# ODB2.net
KiCad netlist of a schematic drawn in EAGLE
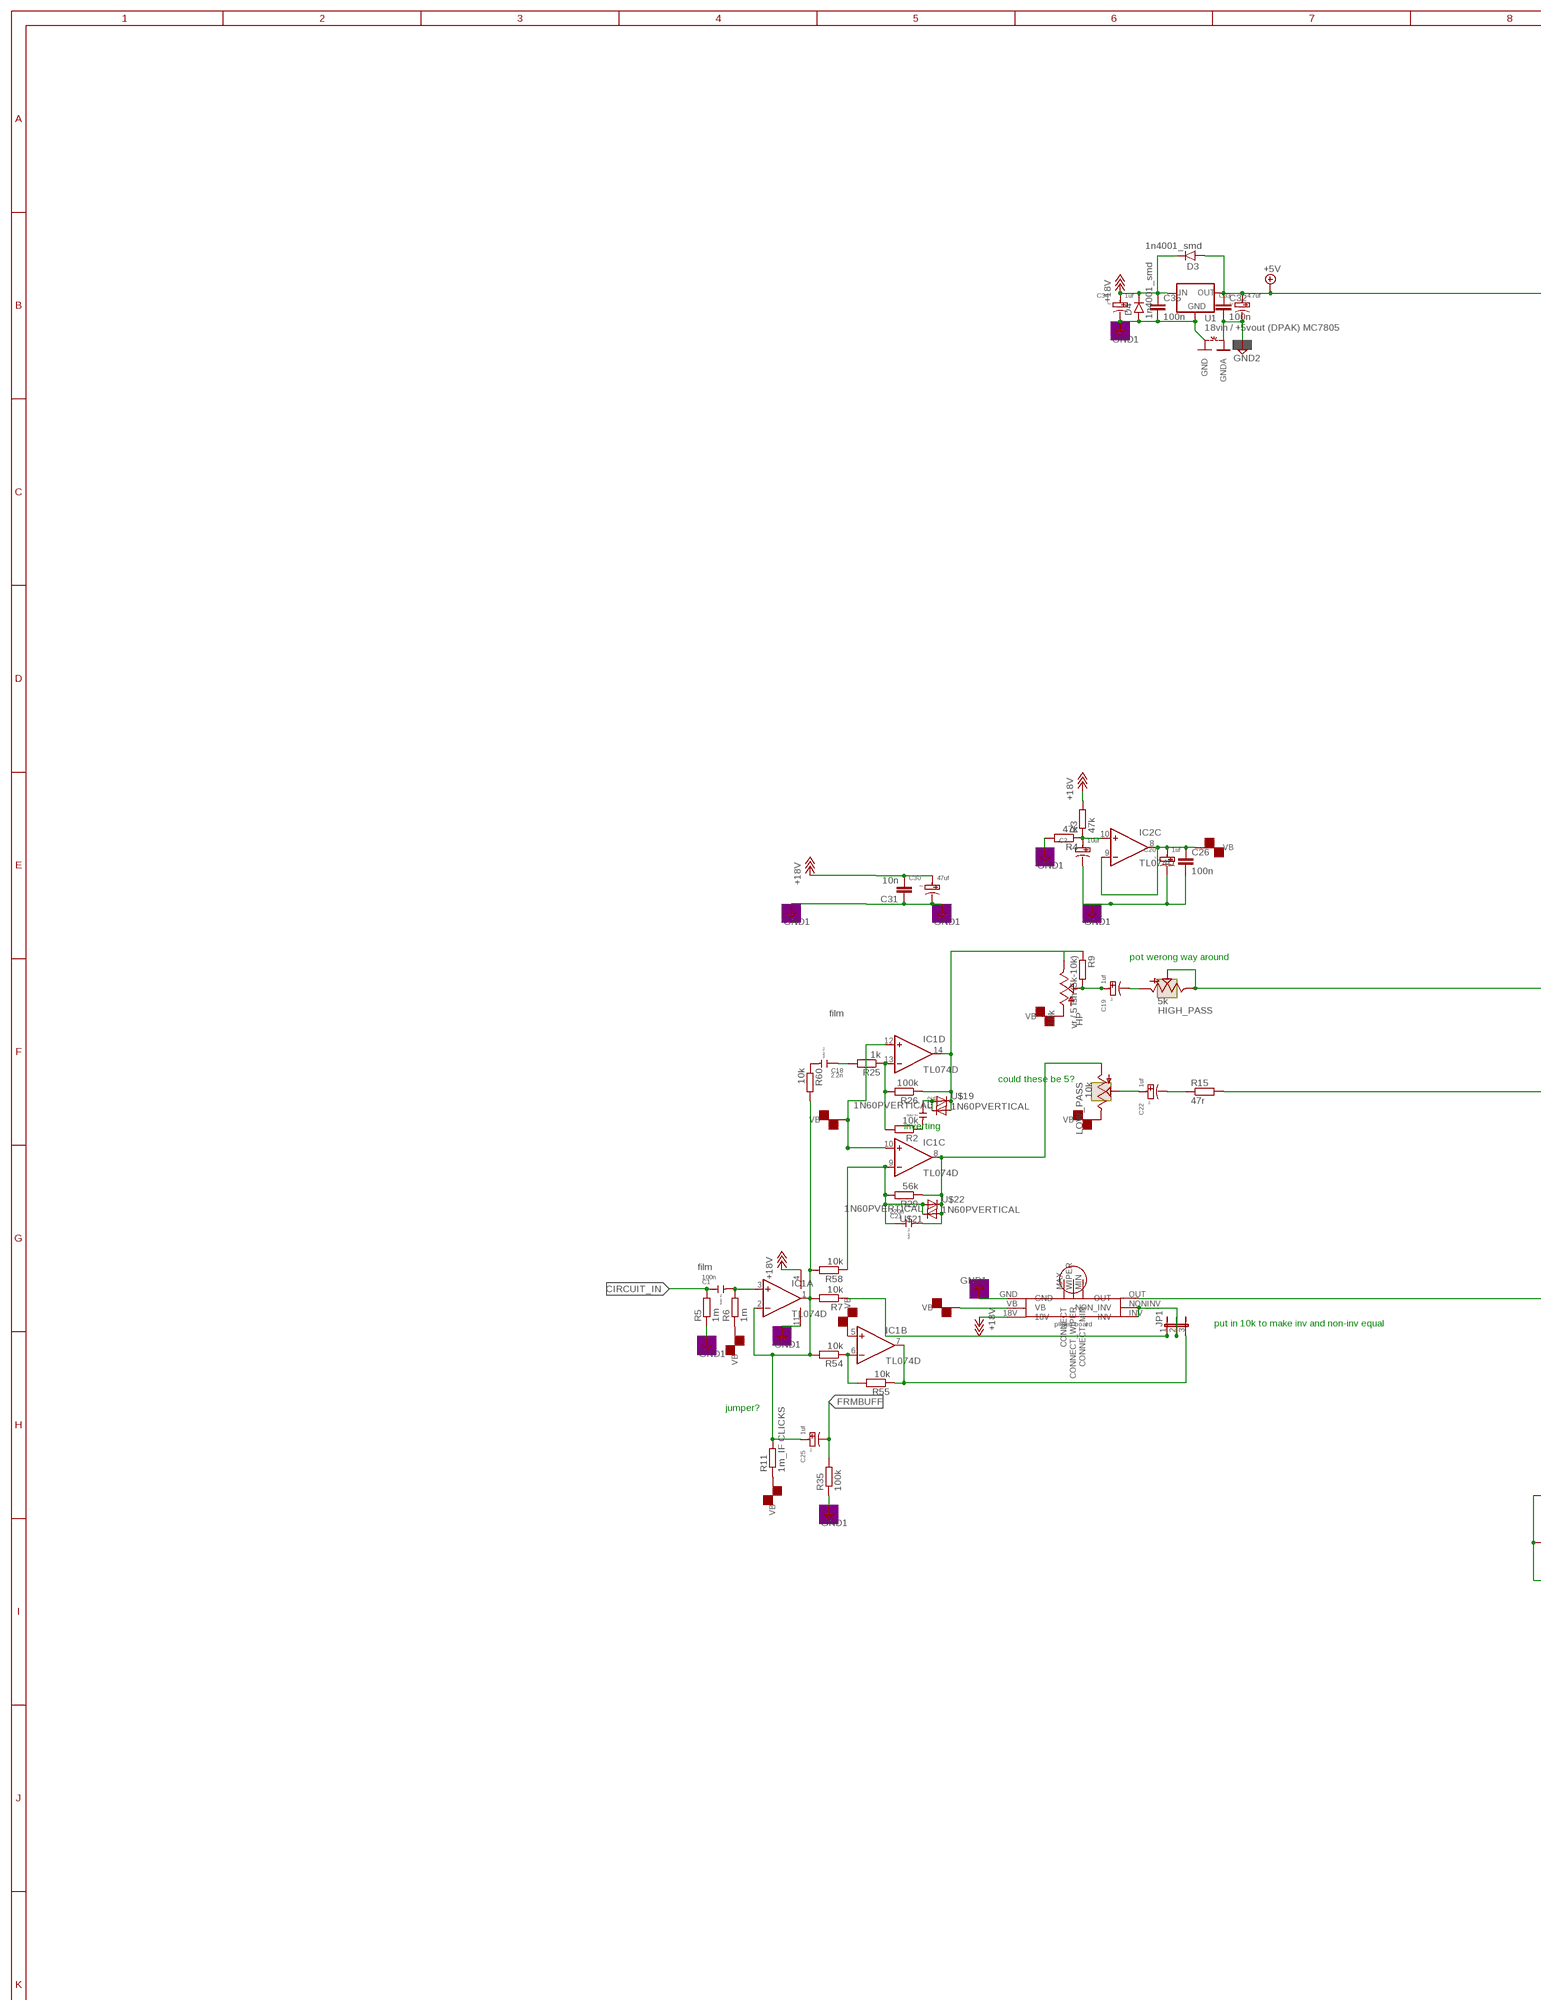
[diagram p0: schematic, sheet 1, part 1 of 3]
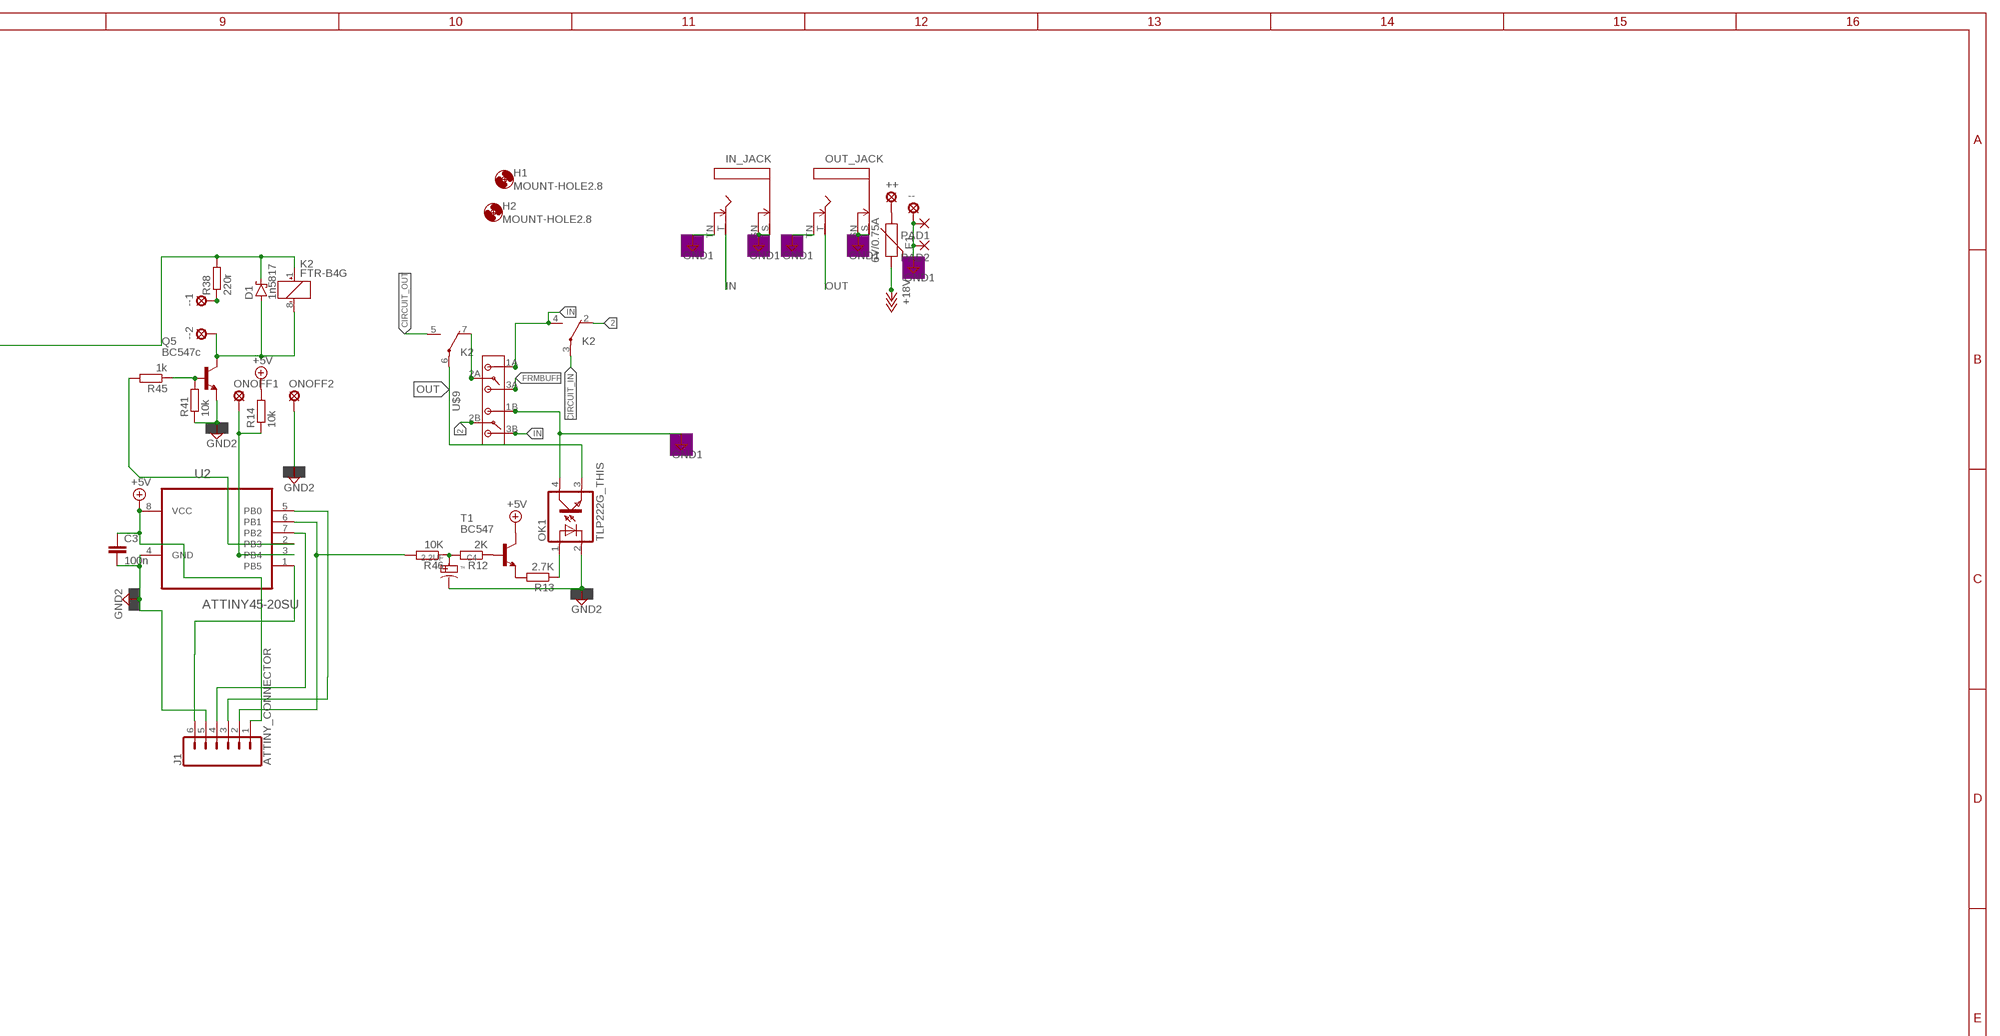
[diagram p1: schematic, sheet 1, part 2 of 3]
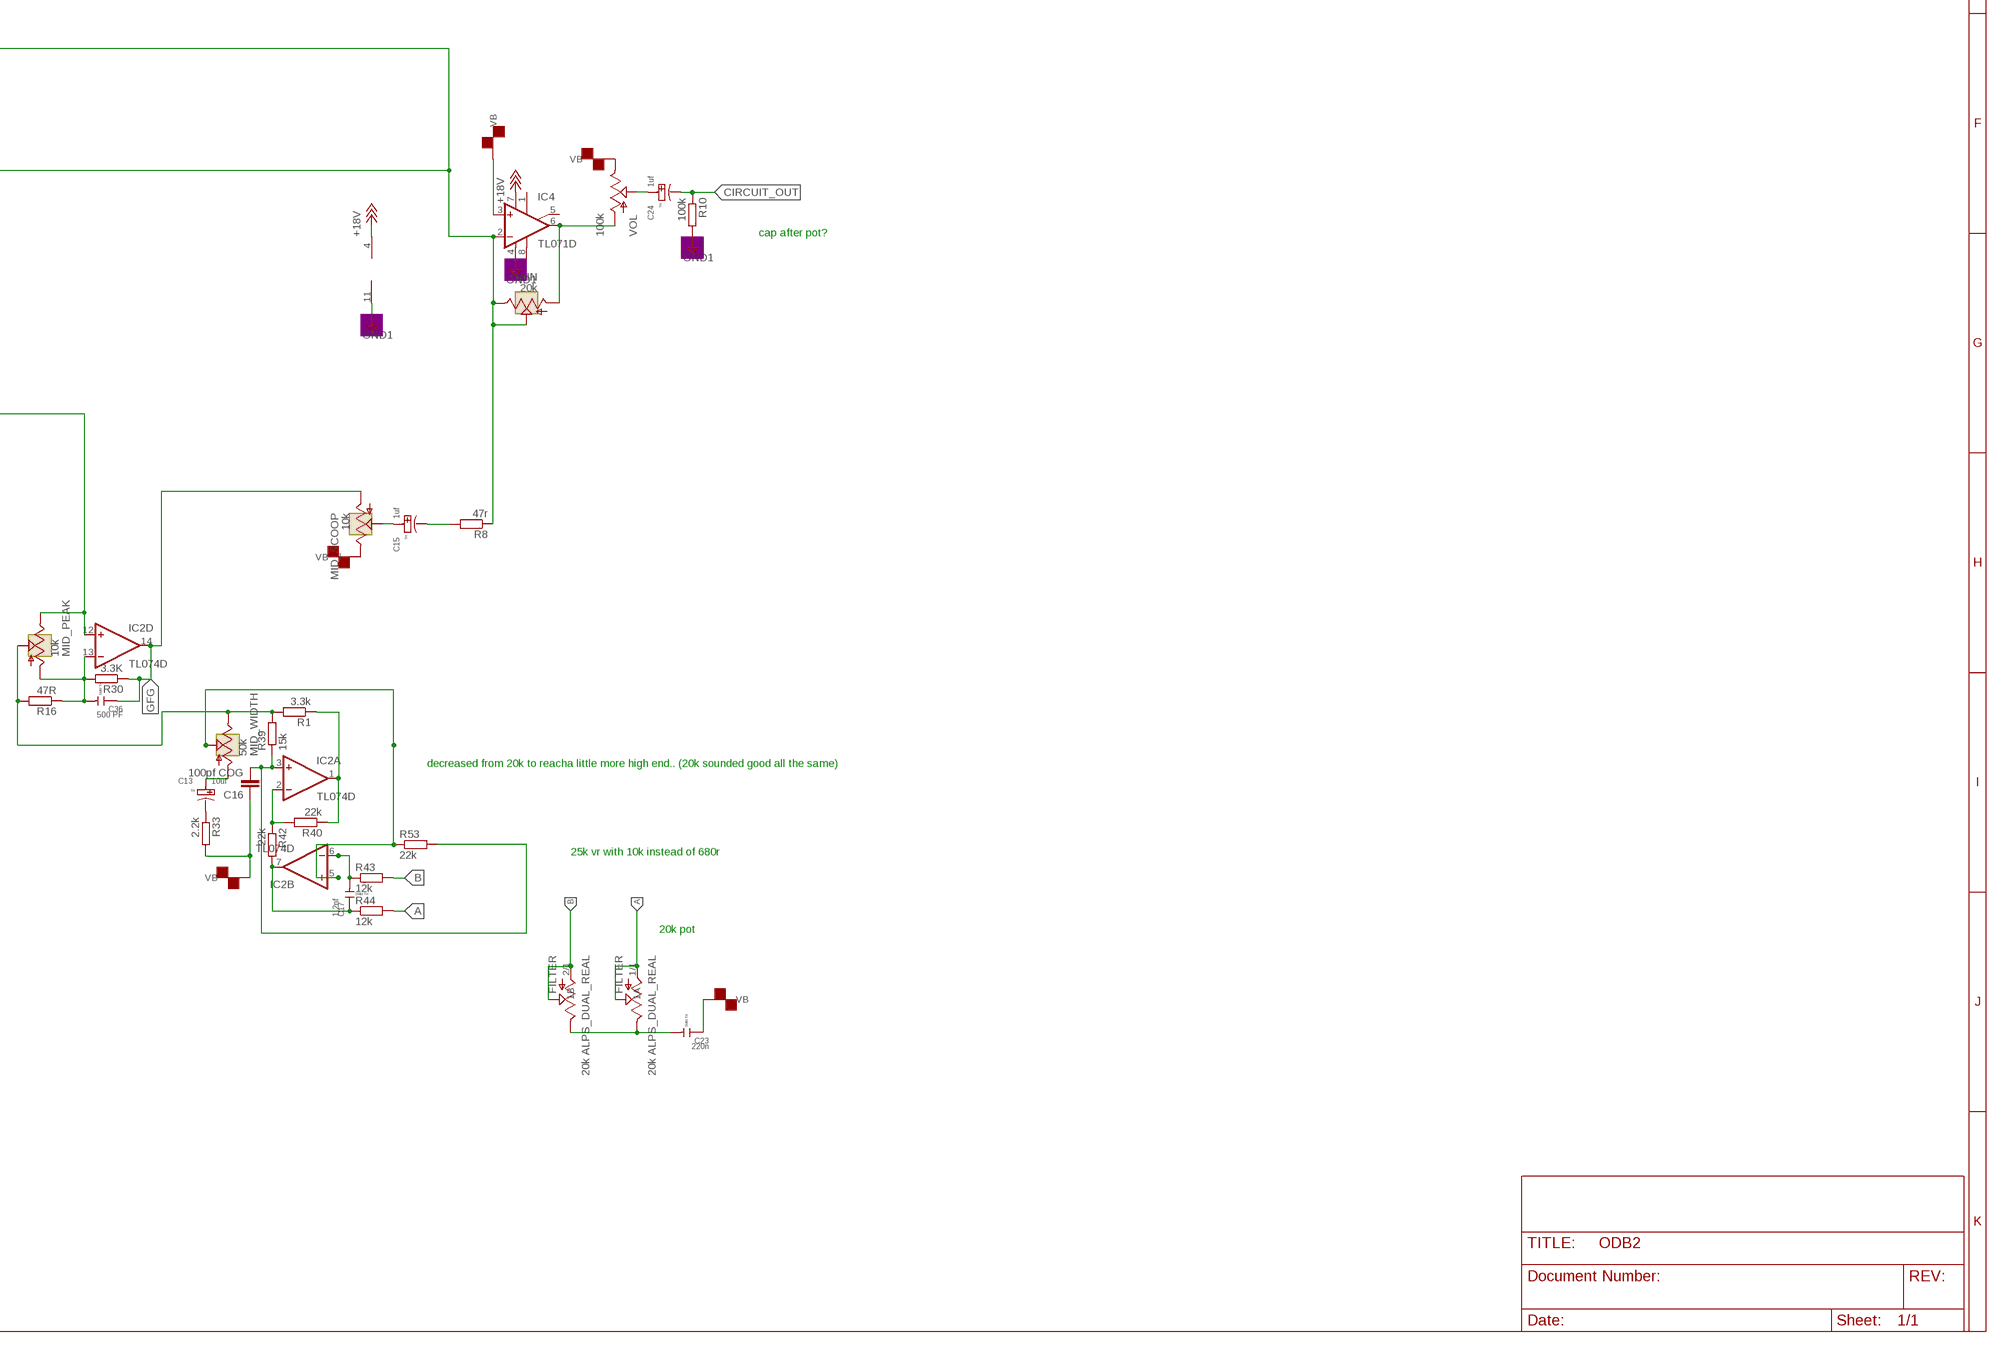
[diagram p2: schematic, sheet 1, part 3 of 3]

(export (version "E")
  (design (tool "Eeschema 10.0.6"))
  (components
    (comp (ref "++")
      (value "LSP10")
      (footprint "eagle-import:LSP10")
      (libsource (lib "eagle-import") (part "LSP10"))
    )
    (comp (ref "--")
      (value "LSP10")
      (footprint "eagle-import:LSP10")
      (libsource (lib "eagle-import") (part "LSP10"))
    )
    (comp (ref "--1")
      (value "LSP10")
      (footprint "eagle-import:LSP10")
      (libsource (lib "eagle-import") (part "LSP10"))
    )
    (comp (ref "--2")
      (value "LSP10")
      (footprint "eagle-import:LSP10")
      (libsource (lib "eagle-import") (part "LSP10"))
    )
    (comp (ref "C1")
      (value "100n")
      (footprint "eagle-import:CERAMIC-5MM")
      (fields (field (name "PACKAGE") "5MM TH"))
      (libsource (lib "eagle-import") (part "THRU_HOLE_5MM_SPACING"))
    )
    (comp (ref "C2")
      (value "10uf")
      (footprint "eagle-import:PC-D5.3MM")
      (fields (field (name "PACKAGE") "TH"))
      (libsource (lib "eagle-import") (part "THRU-HOLE-POLARIZED"))
    )
    (comp (ref "C3")
      (value "100n")
      (footprint "eagle-import:C1206")
      (libsource (lib "eagle-import") (part "resistor_348_C-EUC1206"))
    )
    (comp (ref "C4")
      (value "2.2UF")
      (footprint "eagle-import:PC-D5.3MM")
      (fields (field (name "PACKAGE") "TH"))
      (libsource (lib "eagle-import") (part "THRU-HOLE-POLARIZED"))
    )
    (comp (ref "C12")
      (value "1n")
      (footprint "eagle-import:CERAMIC-5MM")
      (fields (field (name "PACKAGE") "5MM TH"))
      (libsource (lib "eagle-import") (part "THRU_HOLE_5MM_SPACING"))
    )
    (comp (ref "C13")
      (value "10uf")
      (footprint "eagle-import:PC-D5.3MM")
      (fields (field (name "PACKAGE") "TH"))
      (libsource (lib "eagle-import") (part "THRU-HOLE-POLARIZED"))
    )
    (comp (ref "C15")
      (value "1uf")
      (footprint "eagle-import:PC-D5.3MM")
      (fields (field (name "PACKAGE") "TH"))
      (libsource (lib "eagle-import") (part "THRU-HOLE-POLARIZED"))
    )
    (comp (ref "C16")
      (value "100pf COG")
      (footprint "eagle-import:C1206")
      (libsource (lib "eagle-import") (part "resistor_348_C-EUC1206"))
    )
    (comp (ref "C17")
      (value "1.2nf")
      (footprint "eagle-import:CERAMIC-5MM")
      (fields (field (name "PACKAGE") "5MM TH"))
      (libsource (lib "eagle-import") (part "THRU_HOLE_5MM_SPACING"))
    )
    (comp (ref "C18")
      (value "2.2n")
      (footprint "eagle-import:CERAMIC-5MM")
      (fields (field (name "PACKAGE") "5MM TH"))
      (libsource (lib "eagle-import") (part "THRU_HOLE_5MM_SPACING"))
    )
    (comp (ref "C19")
      (value "1uf")
      (footprint "eagle-import:PC-D5.3MM")
      (fields (field (name "PACKAGE") "TH"))
      (libsource (lib "eagle-import") (part "THRU-HOLE-POLARIZED"))
    )
    (comp (ref "C20")
      (value "1uf")
      (footprint "eagle-import:PC-D5.3MM")
      (fields (field (name "PACKAGE") "TH"))
      (libsource (lib "eagle-import") (part "THRU-HOLE-POLARIZED"))
    )
    (comp (ref "C21")
      (value "220n")
      (footprint "eagle-import:CERAMIC-5MM")
      (fields (field (name "PACKAGE") "5MM TH"))
      (libsource (lib "eagle-import") (part "THRU_HOLE_5MM_SPACING"))
    )
    (comp (ref "C22")
      (value "1uf")
      (footprint "eagle-import:PC-D5.3MM")
      (fields (field (name "PACKAGE") "TH"))
      (libsource (lib "eagle-import") (part "THRU-HOLE-POLARIZED"))
    )
    (comp (ref "C23")
      (value "220n")
      (footprint "eagle-import:CERAMIC-5MM")
      (fields (field (name "PACKAGE") "5MM TH"))
      (libsource (lib "eagle-import") (part "THRU_HOLE_5MM_SPACING"))
    )
    (comp (ref "C24")
      (value "1uf")
      (footprint "eagle-import:PC-D5.3MM")
      (fields (field (name "PACKAGE") "TH"))
      (libsource (lib "eagle-import") (part "THRU-HOLE-POLARIZED"))
    )
    (comp (ref "C25")
      (value "1uf")
      (footprint "eagle-import:PC-D5.3MM")
      (fields (field (name "PACKAGE") "TH"))
      (libsource (lib "eagle-import") (part "THRU-HOLE-POLARIZED"))
    )
    (comp (ref "C26")
      (value "100n")
      (footprint "eagle-import:C1206")
      (libsource (lib "eagle-import") (part "resistor_348_C-EUC1206"))
    )
    (comp (ref "C30")
      (value "47uf")
      (footprint "eagle-import:PC-D5.3MM")
      (fields (field (name "PACKAGE") "TH"))
      (libsource (lib "eagle-import") (part "THRU-HOLE-POLARIZED"))
    )
    (comp (ref "C31")
      (value "10n")
      (footprint "eagle-import:C1206")
      (libsource (lib "eagle-import") (part "C-EUC1206"))
    )
    (comp (ref "C32")
      (value "100n")
      (footprint "eagle-import:C1206")
      (libsource (lib "eagle-import") (part "resistor_348_C-EUC1206"))
    )
    (comp (ref "C33")
      (value "4.7uf")
      (footprint "eagle-import:PC-D5.3MM")
      (fields (field (name "PACKAGE") "TH"))
      (libsource (lib "eagle-import") (part "THRU-HOLE-POLARIZED"))
    )
    (comp (ref "C34")
      (value "1uf")
      (footprint "eagle-import:PC-D5.3MM")
      (fields (field (name "PACKAGE") "TH"))
      (libsource (lib "eagle-import") (part "THRU-HOLE-POLARIZED"))
    )
    (comp (ref "C35")
      (value "100n")
      (footprint "eagle-import:C1206")
      (libsource (lib "eagle-import") (part "resistor_348_C-EUC1206"))
    )
    (comp (ref "C36")
      (value "500 PF")
      (footprint "eagle-import:CERAMIC-5MM")
      (fields (field (name "PACKAGE") "5MM TH"))
      (libsource (lib "eagle-import") (part "THRU_HOLE_5MM_SPACING"))
    )
    (comp (ref "D1")
      (value "1n5817")
      (footprint "eagle-import:SMB")
      (libsource (lib "eagle-import") (part "SCHOTTKY-DIODESMD"))
    )
    (comp (ref "D3")
      (value "1n4001_smd")
      (footprint "eagle-import:DO41-1")
      (libsource (lib "eagle-import") (part "1N400X.1"))
    )
    (comp (ref "D4")
      (value "1n4001_smd")
      (footprint "eagle-import:DO41-1")
      (libsource (lib "eagle-import") (part "1N400X.1"))
    )
    (comp (ref "F1")
      (value "6V/0.75A")
      (footprint "eagle-import:1206")
      (libsource (lib "eagle-import") (part "PPTC_THREE-QUARTER-AMP"))
    )
    (comp (ref "FILTER")
      (value "20k ALPS_DUAL_REAL")
      (footprint "eagle-import:ALPS_QUAD")
      (libsource (lib "eagle-import") (part "ALPS_DUAL_REAL"))
    )
    (comp (ref "GAIN")
      (value "20k")
      (footprint "eagle-import:3223G")
      (libsource (lib "eagle-import") (part "TRIM_US-3223G"))
    )
    (comp (ref "H1")
      (value "MOUNT-HOLE2.8")
      (footprint "eagle-import:2,8")
      (libsource (lib "eagle-import") (part "MOUNT-HOLE2.8"))
    )
    (comp (ref "H2")
      (value "MOUNT-HOLE2.8")
      (footprint "eagle-import:2,8")
      (libsource (lib "eagle-import") (part "MOUNT-HOLE2.8"))
    )
    (comp (ref "HIGH_PASS")
      (value "5k")
      (footprint "eagle-import:3223G")
      (libsource (lib "eagle-import") (part "TRIM_US-3223G"))
    )
    (comp (ref "HP")
      (value "10k")
      (footprint "eagle-import:ALPS_POT")
      (libsource (lib "eagle-import") (part "POT"))
    )
    (comp (ref "IC1")
      (value "TL074D")
      (footprint "eagle-import:SO14")
      (libsource (lib "eagle-import") (part "TL074D"))
    )
    (comp (ref "IC2")
      (value "TL074D")
      (footprint "eagle-import:SO14")
      (libsource (lib "eagle-import") (part "TL074D"))
    )
    (comp (ref "IC4")
      (value "TL071D")
      (footprint "eagle-import:SO08")
      (libsource (lib "eagle-import") (part "TL071D"))
    )
    (comp (ref "IN_JACK")
      (value "MMMONNNNOHOLES")
      (footprint "eagle-import:MONONOHOLES")
      (libsource (lib "eagle-import") (part "MMMONNNNOHOLES"))
    )
    (comp (ref "J1")
      (value "ATTINY_CONNECTOR")
      (footprint "eagle-import:1X06_LONGPADS")
      (libsource (lib "eagle-import") (part "CONN_06LONGPADS"))
    )
    (comp (ref "JP1")
      (value "JP2W")
      (footprint "eagle-import:JP2W")
      (libsource (lib "eagle-import") (part "JP2W"))
    )
    (comp (ref "K2")
      (value "FTR-B4G")
      (footprint "eagle-import:FTR-B4G")
      (libsource (lib "eagle-import") (part "FTR-B4G"))
    )
    (comp (ref "LOW_PASS")
      (value "10k")
      (footprint "eagle-import:3223G")
      (libsource (lib "eagle-import") (part "TRIM_US-3223G"))
    )
    (comp (ref "MID_PEAK")
      (value "10k")
      (footprint "eagle-import:3223G")
      (libsource (lib "eagle-import") (part "TRIM_US-3223G"))
    )
    (comp (ref "MID_SCOOP")
      (value "10k")
      (footprint "eagle-import:3223G")
      (libsource (lib "eagle-import") (part "TRIM_US-3223G"))
    )
    (comp (ref "MID_WIDTH")
      (value "50k")
      (footprint "eagle-import:3223G")
      (libsource (lib "eagle-import") (part "TRIM_US-3223G"))
    )
    (comp (ref "OK1")
      (value "TLP222G_THIS")
      (footprint "eagle-import:DIL04")
      (libsource (lib "eagle-import") (part "TLP222G_THIS"))
    )
    (comp (ref "ONOFF1")
      (value "LSP10")
      (footprint "eagle-import:LSP10")
      (libsource (lib "eagle-import") (part "LSP10"))
    )
    (comp (ref "ONOFF2")
      (value "LSP10")
      (footprint "eagle-import:LSP10")
      (libsource (lib "eagle-import") (part "LSP10"))
    )
    (comp (ref "OUT_JACK")
      (value "MMMONNNNOHOLES")
      (footprint "eagle-import:MONONOHOLES")
      (libsource (lib "eagle-import") (part "MMMONNNNOHOLES"))
    )
    (comp (ref "PAD1")
      (value "SMD5")
      (footprint "eagle-import:SMD2,54-5,08")
      (libsource (lib "eagle-import") (part "SMD5"))
    )
    (comp (ref "PAD2")
      (value "SMD5")
      (footprint "eagle-import:SMD2,54-5,08")
      (libsource (lib "eagle-import") (part "SMD5"))
    )
    (comp (ref "Q5")
      (value "BC547c")
      (footprint "eagle-import:TO92")
      (libsource (lib "eagle-import") (part "BC547"))
    )
    (comp (ref "R1")
      (value "3.3k")
      (footprint "eagle-import:R1206")
      (libsource (lib "eagle-import") (part "R-EU_R1206"))
    )
    (comp (ref "R2")
      (value "10k")
      (footprint "eagle-import:R1206")
      (libsource (lib "eagle-import") (part "R-EU_R1206"))
    )
    (comp (ref "R3")
      (value "47k")
      (footprint "eagle-import:R1206")
      (libsource (lib "eagle-import") (part "R-EU_R1206"))
    )
    (comp (ref "R4")
      (value "47k")
      (footprint "eagle-import:R1206")
      (libsource (lib "eagle-import") (part "R-EU_R1206"))
    )
    (comp (ref "R5")
      (value "1m")
      (footprint "eagle-import:R1206")
      (libsource (lib "eagle-import") (part "R-EU_R1206"))
    )
    (comp (ref "R6")
      (value "1m")
      (footprint "eagle-import:R1206")
      (libsource (lib "eagle-import") (part "R-EU_R1206"))
    )
    (comp (ref "R7")
      (value "10k")
      (footprint "eagle-import:R1206")
      (libsource (lib "eagle-import") (part "R-EU_R1206"))
    )
    (comp (ref "R8")
      (value "47r")
      (footprint "eagle-import:R1206")
      (libsource (lib "eagle-import") (part "R-EU_R1206"))
    )
    (comp (ref "R9")
      (value "vr / 5 ish (5k-10k)")
      (footprint "eagle-import:R1206")
      (libsource (lib "eagle-import") (part "R-EU_R1206"))
    )
    (comp (ref "R10")
      (value "100k")
      (footprint "eagle-import:R1206")
      (libsource (lib "eagle-import") (part "R-EU_R1206"))
    )
    (comp (ref "R11")
      (value "1m_IF CLICKS")
      (footprint "eagle-import:R1206")
      (libsource (lib "eagle-import") (part "R-EU_R1206"))
    )
    (comp (ref "R12")
      (value "2K")
      (footprint "eagle-import:M1206")
      (libsource (lib "eagle-import") (part "R-EU_M1206"))
    )
    (comp (ref "R13")
      (value "2.7K")
      (footprint "eagle-import:M1206")
      (libsource (lib "eagle-import") (part "R-EU_M1206"))
    )
    (comp (ref "R14")
      (value "10k")
      (footprint "eagle-import:M1206")
      (libsource (lib "eagle-import") (part "R-EU_M1206"))
    )
    (comp (ref "R15")
      (value "47r")
      (footprint "eagle-import:R1206")
      (libsource (lib "eagle-import") (part "R-EU_R1206"))
    )
    (comp (ref "R16")
      (value "47R")
      (footprint "eagle-import:R1206")
      (libsource (lib "eagle-import") (part "R-EU_R1206"))
    )
    (comp (ref "R25")
      (value "1k")
      (footprint "eagle-import:R1206")
      (libsource (lib "eagle-import") (part "R-EU_R1206"))
    )
    (comp (ref "R26")
      (value "100k")
      (footprint "eagle-import:R1206")
      (libsource (lib "eagle-import") (part "R-EU_R1206"))
    )
    (comp (ref "R29")
      (value "56k")
      (footprint "eagle-import:R1206")
      (libsource (lib "eagle-import") (part "R-EU_R1206"))
    )
    (comp (ref "R30")
      (value "3.3K")
      (footprint "eagle-import:R1206")
      (libsource (lib "eagle-import") (part "R-EU_R1206"))
    )
    (comp (ref "R33")
      (value "2.2k")
      (footprint "eagle-import:R1206")
      (libsource (lib "eagle-import") (part "R-EU_R1206"))
    )
    (comp (ref "R35")
      (value "100k")
      (footprint "eagle-import:R1206")
      (libsource (lib "eagle-import") (part "R-EU_R1206"))
    )
    (comp (ref "R38")
      (value "220r")
      (footprint "eagle-import:M1206")
      (libsource (lib "eagle-import") (part "R-EU_M1206"))
    )
    (comp (ref "R39")
      (value "15k")
      (footprint "eagle-import:R1206")
      (libsource (lib "eagle-import") (part "R-EU_R1206"))
    )
    (comp (ref "R40")
      (value "22k")
      (footprint "eagle-import:R1206")
      (libsource (lib "eagle-import") (part "R-EU_R1206"))
    )
    (comp (ref "R41")
      (value "10k")
      (footprint "eagle-import:M1206")
      (libsource (lib "eagle-import") (part "R-EU_M1206"))
    )
    (comp (ref "R42")
      (value "22k")
      (footprint "eagle-import:R1206")
      (libsource (lib "eagle-import") (part "R-EU_R1206"))
    )
    (comp (ref "R43")
      (value "12k")
      (footprint "eagle-import:R1206")
      (libsource (lib "eagle-import") (part "R-EU_R1206"))
    )
    (comp (ref "R44")
      (value "12k")
      (footprint "eagle-import:R1206")
      (libsource (lib "eagle-import") (part "R-EU_R1206"))
    )
    (comp (ref "R45")
      (value "1k")
      (footprint "eagle-import:M1206")
      (libsource (lib "eagle-import") (part "R-EU_M1206"))
    )
    (comp (ref "R46")
      (value "10K")
      (footprint "eagle-import:M1206")
      (libsource (lib "eagle-import") (part "R-EU_M1206"))
    )
    (comp (ref "R53")
      (value "22k")
      (footprint "eagle-import:R1206")
      (libsource (lib "eagle-import") (part "R-EU_R1206"))
    )
    (comp (ref "R54")
      (value "10k")
      (footprint "eagle-import:R1206")
      (libsource (lib "eagle-import") (part "R-EU_R1206"))
    )
    (comp (ref "R55")
      (value "10k")
      (footprint "eagle-import:R1206")
      (libsource (lib "eagle-import") (part "R-EU_R1206"))
    )
    (comp (ref "R58")
      (value "10k")
      (footprint "eagle-import:R1206")
      (libsource (lib "eagle-import") (part "R-EU_R1206"))
    )
    (comp (ref "R60")
      (value "10k")
      (footprint "eagle-import:R1206")
      (libsource (lib "eagle-import") (part "R-EU_R1206"))
    )
    (comp (ref "T1")
      (value "BC547")
      (footprint "eagle-import:TO92")
      (libsource (lib "eagle-import") (part "transistor_402_BC547"))
    )
    (comp (ref "U$5")
      (value "GT_PLUGIN_ODB")
      (footprint "eagle-import:PLUGIN_RECIEVE_ANOTHER")
      (libsource (lib "eagle-import") (part "GT_PLUGIN_ODB"))
    )
    (comp (ref "U$9")
      (value "BYSWITCH")
      (footprint "eagle-import:BUFF_TRBYPASS")
      (libsource (lib "eagle-import") (part "BYSWITCH"))
    )
    (comp (ref "U$19")
      (value "1N60PVERTICAL")
      (footprint "eagle-import:DO41-1")
      (libsource (lib "eagle-import") (part "1N60PVERTICAL"))
    )
    (comp (ref "U$20")
      (value "1N60PVERTICAL")
      (footprint "eagle-import:DO41-1")
      (libsource (lib "eagle-import") (part "1N60PVERTICAL"))
    )
    (comp (ref "U$21")
      (value "1N60PVERTICAL")
      (footprint "eagle-import:DO41-1")
      (libsource (lib "eagle-import") (part "1N60PVERTICAL"))
    )
    (comp (ref "U$22")
      (value "1N60PVERTICAL")
      (footprint "eagle-import:DO41-1")
      (libsource (lib "eagle-import") (part "1N60PVERTICAL"))
    )
    (comp (ref "U1")
      (value "18vin / +5vout (DPAK) MC7805")
      (footprint "eagle-import:TO-252")
      (libsource (lib "eagle-import") (part "V_REG_78XX7812"))
    )
    (comp (ref "U2")
      (value "ATTINY45-20SU")
      (footprint "eagle-import:SOIC127P798X216-8N")
      (libsource (lib "eagle-import") (part "ATTINY45-20SU"))
    )
    (comp (ref "VOL")
      (value "100k")
      (footprint "eagle-import:ALPS_POT")
      (libsource (lib "eagle-import") (part "POT"))
    )
    (comp (ref "~NUDEV~1")
      (value "GND-GNDA1,27MM")
      (footprint "eagle-import:GND-GNDA-1,27MM")
      (libsource (lib "eagle-import") (part "GND-GNDA1,27MM"))
    )
  )
  (nets
    (net (code "1") (name "+5V") (class "Default")
      (node (ref "C3") (pin "1") (pinfunction "1_1") (pintype "passive"))
      (node (ref "C32") (pin "1") (pinfunction "1_1") (pintype "passive"))
      (node (ref "C33") (pin "+") (pinfunction "+_+") (pintype "passive"))
      (node (ref "D1") (pin "C") (pinfunction "C_C") (pintype "passive"))
      (node (ref "D3") (pin "A") (pinfunction "A_A") (pintype "passive"))
      (node (ref "J1") (pin "1") (pinfunction "1_1") (pintype "passive"))
      (node (ref "K2") (pin "1") (pinfunction "+_1") (pintype "passive"))
      (node (ref "R14") (pin "2") (pinfunction "2_2") (pintype "passive"))
      (node (ref "R38") (pin "2") (pinfunction "2_2") (pintype "passive"))
      (node (ref "T1") (pin "3") (pinfunction "C_3") (pintype "passive"))
      (node (ref "U1") (pin "2") (pinfunction "OUT_2") (pintype "passive"))
      (node (ref "U2") (pin "8") (pinfunction "VCC_8") (pintype "power_in"))
    )
    (net (code "2") (name "+18V") (class "Default")
      (node (ref "C30") (pin "+") (pinfunction "+_+") (pintype "passive"))
      (node (ref "C31") (pin "2") (pinfunction "2_2") (pintype "passive"))
      (node (ref "C34") (pin "+") (pinfunction "+_+") (pintype "passive"))
      (node (ref "C35") (pin "1") (pinfunction "1_1") (pintype "passive"))
      (node (ref "D3") (pin "C") (pinfunction "C_C") (pintype "passive"))
      (node (ref "D4") (pin "C") (pinfunction "C_C") (pintype "passive"))
      (node (ref "F1") (pin "2") (pinfunction "2_2") (pintype "bidirectional"))
      (node (ref "IC1") (pin "4") (pinfunction "V+_4") (pintype "power_in"))
      (node (ref "IC2") (pin "4") (pinfunction "V+_4") (pintype "power_in"))
      (node (ref "IC4") (pin "7") (pinfunction "V+_7") (pintype "power_in"))
      (node (ref "R3") (pin "2") (pinfunction "2_2") (pintype "passive"))
      (node (ref "U$5") (pin "18V") (pinfunction "18V_18V") (pintype "bidirectional"))
      (node (ref "U1") (pin "1") (pinfunction "IN_1") (pintype "input"))
    )
    (net (code "3") (name "2") (class "Default")
      (node (ref "K2") (pin "2") (pinfunction "O_2") (pintype "passive"))
      (node (ref "U$9") (pin "2B") (pinfunction "2B_2B") (pintype "passive"))
    )
    (net (code "4") (name "A") (class "Default")
      (node (ref "FILTER") (pin "1/1") (pinfunction "1A_1/1") (pintype "passive"))
      (node (ref "FILTER") (pin "1/2") (pinfunction "2A_1/2") (pintype "passive"))
      (node (ref "R44") (pin "2") (pinfunction "2_2") (pintype "passive"))
    )
    (net (code "5") (name "B") (class "Default")
      (node (ref "FILTER") (pin "2/1") (pinfunction "1B_2/1") (pintype "passive"))
      (node (ref "FILTER") (pin "2/2") (pinfunction "2B_2/2") (pintype "passive"))
      (node (ref "R43") (pin "2") (pinfunction "2_2") (pintype "passive"))
    )
    (net (code "6") (name "CIRCUIT_IN") (class "Default")
      (node (ref "C1") (pin "1") (pinfunction "1_1") (pintype "passive"))
      (node (ref "K2") (pin "3") (pinfunction "P_3") (pintype "passive"))
      (node (ref "R5") (pin "2") (pinfunction "2_2") (pintype "passive"))
    )
    (net (code "7") (name "CIRCUIT_OUT") (class "Default")
      (node (ref "C24") (pin "-") (pinfunction "-_-") (pintype "passive"))
      (node (ref "K2") (pin "5") (pinfunction "S_5") (pintype "passive"))
      (node (ref "R10") (pin "1") (pinfunction "1_1") (pintype "passive"))
    )
    (net (code "8") (name "FRMBUFF") (class "Default")
      (node (ref "C25") (pin "-") (pinfunction "-_-") (pintype "passive"))
      (node (ref "R35") (pin "2") (pinfunction "2_2") (pintype "passive"))
      (node (ref "U$9") (pin "3A") (pinfunction "3A_3A") (pintype "passive"))
    )
    (net (code "9") (name "GFG") (class "Default")
      (node (ref "C36") (pin "1") (pinfunction "1_1") (pintype "passive"))
      (node (ref "IC2") (pin "14") (pinfunction "OUT_14") (pintype "output"))
      (node (ref "MID_SCOOP") (pin "1") (pinfunction "A_1") (pintype "passive"))
      (node (ref "R30") (pin "1") (pinfunction "1_1") (pintype "passive"))
    )
    (net (code "10") (name "GND1") (class "Default")
      (node (ref "--") (pin "MP") (pinfunction "MP_MP") (pintype "passive"))
      (node (ref "C2") (pin "-") (pinfunction "-_-") (pintype "passive"))
      (node (ref "C20") (pin "-") (pinfunction "-_-") (pintype "passive"))
      (node (ref "C26") (pin "2") (pinfunction "2_2") (pintype "passive"))
      (node (ref "C30") (pin "-") (pinfunction "-_-") (pintype "passive"))
      (node (ref "C31") (pin "1") (pinfunction "1_1") (pintype "passive"))
      (node (ref "C34") (pin "-") (pinfunction "-_-") (pintype "passive"))
      (node (ref "C35") (pin "2") (pinfunction "2_2") (pintype "passive"))
      (node (ref "D4") (pin "A") (pinfunction "A_A") (pintype "passive"))
      (node (ref "IC1") (pin "11") (pinfunction "V-_11") (pintype "power_in"))
      (node (ref "IC2") (pin "11") (pinfunction "V-_11") (pintype "power_in"))
      (node (ref "IC4") (pin "4") (pinfunction "V-_4") (pintype "power_in"))
      (node (ref "IN_JACK") (pin "S") (pinfunction "S_S") (pintype "passive"))
      (node (ref "IN_JACK") (pin "SN") (pinfunction "SN_SN") (pintype "passive"))
      (node (ref "IN_JACK") (pin "TN") (pinfunction "TN_TN") (pintype "passive"))
      (node (ref "OK1") (pin "4") (pinfunction "COL_4") (pintype "passive"))
      (node (ref "OUT_JACK") (pin "S") (pinfunction "S_S") (pintype "passive"))
      (node (ref "OUT_JACK") (pin "SN") (pinfunction "SN_SN") (pintype "passive"))
      (node (ref "OUT_JACK") (pin "TN") (pinfunction "TN_TN") (pintype "passive"))
      (node (ref "PAD1") (pin "1") (pinfunction "P_1") (pintype "passive"))
      (node (ref "PAD2") (pin "1") (pinfunction "P_1") (pintype "passive"))
      (node (ref "R10") (pin "2") (pinfunction "2_2") (pintype "passive"))
      (node (ref "R35") (pin "1") (pinfunction "1_1") (pintype "passive"))
      (node (ref "R4") (pin "2") (pinfunction "2_2") (pintype "passive"))
      (node (ref "R5") (pin "1") (pinfunction "1_1") (pintype "passive"))
      (node (ref "U$5") (pin "GND") (pinfunction "GND_GND") (pintype "bidirectional"))
      (node (ref "U$9") (pin "1B") (pinfunction "1B_1B") (pintype "passive"))
      (node (ref "U1") (pin "3") (pinfunction "GND_3") (pintype "input"))
      (node (ref "~NUDEV~1") (pin "GND") (pinfunction "GND_GND") (pintype "power_in"))
    )
    (net (code "11") (name "GND2") (class "Default")
      (node (ref "C3") (pin "2") (pinfunction "2_2") (pintype "passive"))
      (node (ref "C32") (pin "2") (pinfunction "2_2") (pintype "passive"))
      (node (ref "C33") (pin "-") (pinfunction "-_-") (pintype "passive"))
      (node (ref "C4") (pin "-") (pinfunction "-_-") (pintype "passive"))
      (node (ref "J1") (pin "5") (pinfunction "5_5") (pintype "passive"))
      (node (ref "OK1") (pin "2") (pinfunction "C_2") (pintype "passive"))
      (node (ref "ONOFF2") (pin "MP") (pinfunction "MP_MP") (pintype "passive"))
      (node (ref "Q5") (pin "1") (pinfunction "E_1") (pintype "passive"))
      (node (ref "R41") (pin "1") (pinfunction "1_1") (pintype "passive"))
      (node (ref "U2") (pin "4") (pinfunction "GND_4") (pintype "passive"))
      (node (ref "~NUDEV~1") (pin "GNDA") (pinfunction "GNDA_GNDA") (pintype "power_in"))
    )
    (net (code "12") (name "IN") (class "Default")
      (node (ref "IN_JACK") (pin "T") (pinfunction "T_T") (pintype "passive"))
      (node (ref "K2") (pin "4") (pinfunction "S_4") (pintype "passive"))
      (node (ref "U$9") (pin "1A") (pinfunction "1A_1A") (pintype "passive"))
      (node (ref "U$9") (pin "3B") (pinfunction "3B_3B") (pintype "passive"))
    )
    (net (code "13") (name "Net-(++-PadMP)") (class "Default")
      (node (ref "++") (pin "MP") (pinfunction "MP_MP") (pintype "passive"))
      (node (ref "F1") (pin "1") (pinfunction "1_1") (pintype "bidirectional"))
    )
    (net (code "14") (name "Net-(--1-PadMP)") (class "Default")
      (node (ref "--1") (pin "MP") (pinfunction "MP_MP") (pintype "passive"))
      (node (ref "R38") (pin "1") (pinfunction "1_1") (pintype "passive"))
    )
    (net (code "15") (name "Net-(C4-Pad+)") (class "Default")
      (node (ref "C4") (pin "+") (pinfunction "+_+") (pintype "passive"))
      (node (ref "R12") (pin "2") (pinfunction "2_2") (pintype "passive"))
      (node (ref "R46") (pin "1") (pinfunction "1_1") (pintype "passive"))
    )
    (net (code "16") (name "Net-(C12-Pad1)") (class "Default")
      (node (ref "C12") (pin "1") (pinfunction "1_1") (pintype "passive"))
      (node (ref "U$19") (pin "A") (pinfunction "A_A") (pintype "passive"))
      (node (ref "U$20") (pin "C") (pinfunction "C_C") (pintype "passive"))
    )
    (net (code "17") (name "Net-(C12-Pad2)") (class "Default")
      (node (ref "C12") (pin "2") (pinfunction "2_2") (pintype "passive"))
      (node (ref "R2") (pin "1") (pinfunction "1_1") (pintype "passive"))
    )
    (net (code "18") (name "Net-(C13-Pad-)") (class "Default")
      (node (ref "C13") (pin "-") (pinfunction "-_-") (pintype "passive"))
      (node (ref "R33") (pin "1") (pinfunction "1_1") (pintype "passive"))
    )
    (net (code "19") (name "Net-(C15-Pad-)") (class "Default")
      (node (ref "C15") (pin "-") (pinfunction "-_-") (pintype "passive"))
      (node (ref "R8") (pin "2") (pinfunction "2_2") (pintype "passive"))
    )
    (net (code "20") (name "Net-(C18-Pad1)") (class "Default")
      (node (ref "C18") (pin "1") (pinfunction "1_1") (pintype "passive"))
      (node (ref "R25") (pin "2") (pinfunction "2_2") (pintype "passive"))
    )
    (net (code "21") (name "Net-(C18-Pad2)") (class "Default")
      (node (ref "C18") (pin "2") (pinfunction "2_2") (pintype "passive"))
      (node (ref "R60") (pin "1") (pinfunction "1_1") (pintype "passive"))
    )
    (net (code "22") (name "Net-(C22-Pad-)") (class "Default")
      (node (ref "C22") (pin "-") (pinfunction "-_-") (pintype "passive"))
      (node (ref "R15") (pin "1") (pinfunction "1_1") (pintype "passive"))
    )
    (net (code "23") (name "Net-(FILTER-3A)") (class "Default")
      (node (ref "C23") (pin "2") (pinfunction "2_2") (pintype "passive"))
      (node (ref "FILTER") (pin "1/3") (pinfunction "3A_1/3") (pintype "passive"))
      (node (ref "FILTER") (pin "2/3") (pinfunction "3B_2/3") (pintype "passive"))
    )
    (net (code "24") (name "Net-(GAIN-A)") (class "Default")
      (node (ref "GAIN") (pin "1") (pinfunction "A_1") (pintype "passive"))
      (node (ref "IC4") (pin "6") (pinfunction "OUT_6") (pintype "output"))
      (node (ref "VOL") (pin "P$3") (pinfunction "A_P$3") (pintype "passive"))
    )
    (net (code "25") (name "Net-(GAIN-E)") (class "Default")
      (node (ref "GAIN") (pin "2") (pinfunction "S_2") (pintype "passive"))
      (node (ref "GAIN") (pin "3") (pinfunction "E_3") (pintype "passive"))
      (node (ref "HIGH_PASS") (pin "2") (pinfunction "S_2") (pintype "passive"))
      (node (ref "HIGH_PASS") (pin "3") (pinfunction "E_3") (pintype "passive"))
      (node (ref "IC4") (pin "2") (pinfunction "-IN_2") (pintype "input"))
      (node (ref "R15") (pin "2") (pinfunction "2_2") (pintype "passive"))
      (node (ref "R8") (pin "1") (pinfunction "1_1") (pintype "passive"))
    )
    (net (code "26") (name "Net-(HIGH_PASS-A)") (class "Default")
      (node (ref "C19") (pin "-") (pinfunction "-_-") (pintype "passive"))
      (node (ref "HIGH_PASS") (pin "1") (pinfunction "A_1") (pintype "passive"))
    )
    (net (code "27") (name "Net-(HP-E)") (class "Default")
      (node (ref "HP") (pin "P$1") (pinfunction "E_P$1") (pintype "passive"))
      (node (ref "IC1") (pin "14") (pinfunction "OUT_14") (pintype "output"))
      (node (ref "R26") (pin "1") (pinfunction "1_1") (pintype "passive"))
      (node (ref "R9") (pin "1") (pinfunction "1_1") (pintype "passive"))
      (node (ref "U$19") (pin "C") (pinfunction "C_C") (pintype "passive"))
      (node (ref "U$20") (pin "A") (pinfunction "A_A") (pintype "passive"))
    )
    (net (code "28") (name "Net-(HP-S)") (class "Default")
      (node (ref "C19") (pin "+") (pinfunction "+_+") (pintype "passive"))
      (node (ref "HP") (pin "P$2") (pinfunction "S_P$2") (pintype "passive"))
      (node (ref "R9") (pin "2") (pinfunction "2_2") (pintype "passive"))
    )
    (net (code "29") (name "Net-(IC1A-+IN)") (class "Default")
      (node (ref "C1") (pin "2") (pinfunction "2_2") (pintype "passive"))
      (node (ref "IC1") (pin "3") (pinfunction "+IN_3") (pintype "input"))
      (node (ref "R6") (pin "2") (pinfunction "2_2") (pintype "passive"))
    )
    (net (code "30") (name "Net-(IC1A--IN)") (class "Default")
      (node (ref "C25") (pin "+") (pinfunction "+_+") (pintype "passive"))
      (node (ref "IC1") (pin "1") (pinfunction "OUT_1") (pintype "output"))
      (node (ref "IC1") (pin "2") (pinfunction "-IN_2") (pintype "input"))
      (node (ref "R11") (pin "2") (pinfunction "2_2") (pintype "passive"))
      (node (ref "R54") (pin "2") (pinfunction "2_2") (pintype "passive"))
      (node (ref "R58") (pin "2") (pinfunction "2_2") (pintype "passive"))
      (node (ref "R60") (pin "2") (pinfunction "2_2") (pintype "passive"))
      (node (ref "R7") (pin "2") (pinfunction "2_2") (pintype "passive"))
    )
    (net (code "31") (name "Net-(IC1B--IN)") (class "Default")
      (node (ref "IC1") (pin "6") (pinfunction "-IN_6") (pintype "input"))
      (node (ref "R54") (pin "1") (pinfunction "1_1") (pintype "passive"))
      (node (ref "R55") (pin "2") (pinfunction "2_2") (pintype "passive"))
    )
    (net (code "32") (name "Net-(IC1B-OUT)") (class "Default")
      (node (ref "IC1") (pin "7") (pinfunction "OUT_7") (pintype "output"))
      (node (ref "JP1") (pin "3") (pinfunction "3_3") (pintype "passive"))
      (node (ref "R55") (pin "1") (pinfunction "1_1") (pintype "passive"))
    )
    (net (code "33") (name "Net-(IC1C--IN)") (class "Default")
      (node (ref "C21") (pin "1") (pinfunction "1_1") (pintype "passive"))
      (node (ref "IC1") (pin "9") (pinfunction "-IN_9") (pintype "input"))
      (node (ref "R29") (pin "2") (pinfunction "2_2") (pintype "passive"))
      (node (ref "R58") (pin "1") (pinfunction "1_1") (pintype "passive"))
      (node (ref "U$21") (pin "C") (pinfunction "C_C") (pintype "passive"))
      (node (ref "U$22") (pin "A") (pinfunction "A_A") (pintype "passive"))
    )
    (net (code "34") (name "Net-(IC1C-OUT)") (class "Default")
      (node (ref "C21") (pin "2") (pinfunction "2_2") (pintype "passive"))
      (node (ref "IC1") (pin "8") (pinfunction "OUT_8") (pintype "output"))
      (node (ref "LOW_PASS") (pin "1") (pinfunction "A_1") (pintype "passive"))
      (node (ref "R29") (pin "1") (pinfunction "1_1") (pintype "passive"))
      (node (ref "U$21") (pin "A") (pinfunction "A_A") (pintype "passive"))
      (node (ref "U$22") (pin "C") (pinfunction "C_C") (pintype "passive"))
    )
    (net (code "35") (name "Net-(IC1D--IN)") (class "Default")
      (node (ref "IC1") (pin "13") (pinfunction "-IN_13") (pintype "input"))
      (node (ref "R2") (pin "2") (pinfunction "2_2") (pintype "passive"))
      (node (ref "R25") (pin "1") (pinfunction "1_1") (pintype "passive"))
      (node (ref "R26") (pin "2") (pinfunction "2_2") (pintype "passive"))
    )
    (net (code "36") (name "Net-(IC2A-+IN)") (class "Default")
      (node (ref "C16") (pin "2") (pinfunction "2_2") (pintype "passive"))
      (node (ref "IC2") (pin "3") (pinfunction "+IN_3") (pintype "input"))
      (node (ref "R39") (pin "1") (pinfunction "1_1") (pintype "passive"))
      (node (ref "R53") (pin "2") (pinfunction "2_2") (pintype "passive"))
    )
    (net (code "37") (name "Net-(IC2A--IN)") (class "Default")
      (node (ref "IC2") (pin "2") (pinfunction "-IN_2") (pintype "input"))
      (node (ref "R40") (pin "2") (pinfunction "2_2") (pintype "passive"))
      (node (ref "R42") (pin "1") (pinfunction "1_1") (pintype "passive"))
    )
    (net (code "38") (name "Net-(IC2A-OUT)") (class "Default")
      (node (ref "IC2") (pin "1") (pinfunction "OUT_1") (pintype "output"))
      (node (ref "R1") (pin "1") (pinfunction "1_1") (pintype "passive"))
      (node (ref "R40") (pin "1") (pinfunction "1_1") (pintype "passive"))
    )
    (net (code "39") (name "Net-(IC2B-+IN)") (class "Default")
      (node (ref "IC2") (pin "5") (pinfunction "+IN_5") (pintype "input"))
      (node (ref "MID_WIDTH") (pin "2") (pinfunction "S_2") (pintype "passive"))
      (node (ref "R53") (pin "1") (pinfunction "1_1") (pintype "passive"))
    )
    (net (code "40") (name "Net-(IC2B--IN)") (class "Default")
      (node (ref "C17") (pin "2") (pinfunction "2_2") (pintype "passive"))
      (node (ref "IC2") (pin "6") (pinfunction "-IN_6") (pintype "input"))
      (node (ref "R43") (pin "1") (pinfunction "1_1") (pintype "passive"))
    )
    (net (code "41") (name "Net-(IC2B-OUT)") (class "Default")
      (node (ref "C17") (pin "1") (pinfunction "1_1") (pintype "passive"))
      (node (ref "IC2") (pin "7") (pinfunction "OUT_7") (pintype "output"))
      (node (ref "R42") (pin "2") (pinfunction "2_2") (pintype "passive"))
      (node (ref "R44") (pin "1") (pinfunction "1_1") (pintype "passive"))
    )
    (net (code "42") (name "Net-(IC2C-+IN)") (class "Default")
      (node (ref "C2") (pin "+") (pinfunction "+_+") (pintype "passive"))
      (node (ref "IC2") (pin "10") (pinfunction "+IN_10") (pintype "input"))
      (node (ref "R3") (pin "1") (pinfunction "1_1") (pintype "passive"))
      (node (ref "R4") (pin "1") (pinfunction "1_1") (pintype "passive"))
    )
    (net (code "43") (name "Net-(IC2D-+IN)") (class "Default")
      (node (ref "IC2") (pin "12") (pinfunction "+IN_12") (pintype "input"))
      (node (ref "MID_PEAK") (pin "3") (pinfunction "E_3") (pintype "passive"))
      (node (ref "U$5") (pin "OUT") (pinfunction "OUT_OUT") (pintype "bidirectional"))
    )
    (net (code "44") (name "Net-(IC2D--IN)") (class "Default")
      (node (ref "C36") (pin "2") (pinfunction "2_2") (pintype "passive"))
      (node (ref "IC2") (pin "13") (pinfunction "-IN_13") (pintype "input"))
      (node (ref "MID_PEAK") (pin "1") (pinfunction "A_1") (pintype "passive"))
      (node (ref "R16") (pin "1") (pinfunction "1_1") (pintype "passive"))
      (node (ref "R30") (pin "2") (pinfunction "2_2") (pintype "passive"))
    )
    (net (code "45") (name "Net-(JP1-Pad1)") (class "Default")
      (node (ref "JP1") (pin "1") (pinfunction "1_1") (pintype "passive"))
      (node (ref "R7") (pin "1") (pinfunction "1_1") (pintype "passive"))
    )
    (net (code "46") (name "Net-(K2B-O)") (class "Default")
      (node (ref "K2") (pin "7") (pinfunction "O_7") (pintype "passive"))
      (node (ref "U$9") (pin "2A") (pinfunction "2A_2A") (pintype "passive"))
    )
    (net (code "47") (name "Net-(K2C--)") (class "Default")
      (node (ref "--2") (pin "MP") (pinfunction "MP_MP") (pintype "passive"))
      (node (ref "D1") (pin "A") (pinfunction "A_A") (pintype "passive"))
      (node (ref "K2") (pin "8") (pinfunction "-_8") (pintype "passive"))
      (node (ref "Q5") (pin "3") (pinfunction "C_3") (pintype "passive"))
    )
    (net (code "48") (name "Net-(LOW_PASS-S)") (class "Default")
      (node (ref "C22") (pin "+") (pinfunction "+_+") (pintype "passive"))
      (node (ref "LOW_PASS") (pin "2") (pinfunction "S_2") (pintype "passive"))
    )
    (net (code "49") (name "Net-(MID_PEAK-S)") (class "Default")
      (node (ref "MID_PEAK") (pin "2") (pinfunction "S_2") (pintype "passive"))
      (node (ref "MID_WIDTH") (pin "3") (pinfunction "E_3") (pintype "passive"))
      (node (ref "R1") (pin "2") (pinfunction "2_2") (pintype "passive"))
      (node (ref "R16") (pin "2") (pinfunction "2_2") (pintype "passive"))
      (node (ref "R39") (pin "2") (pinfunction "2_2") (pintype "passive"))
    )
    (net (code "50") (name "Net-(MID_SCOOP-S)") (class "Default")
      (node (ref "C15") (pin "+") (pinfunction "+_+") (pintype "passive"))
      (node (ref "MID_SCOOP") (pin "2") (pinfunction "S_2") (pintype "passive"))
    )
    (net (code "51") (name "Net-(MID_WIDTH-A)") (class "Default")
      (node (ref "C13") (pin "+") (pinfunction "+_+") (pintype "passive"))
      (node (ref "MID_WIDTH") (pin "1") (pinfunction "A_1") (pintype "passive"))
    )
    (net (code "52") (name "Net-(OK1-A)") (class "Default")
      (node (ref "OK1") (pin "1") (pinfunction "A_1") (pintype "passive"))
      (node (ref "R13") (pin "1") (pinfunction "1_1") (pintype "passive"))
    )
    (net (code "53") (name "Net-(Q5-B)") (class "Default")
      (node (ref "Q5") (pin "2") (pinfunction "B_2") (pintype "passive"))
      (node (ref "R41") (pin "2") (pinfunction "2_2") (pintype "passive"))
      (node (ref "R45") (pin "1") (pinfunction "1_1") (pintype "passive"))
    )
    (net (code "54") (name "Net-(T1-B)") (class "Default")
      (node (ref "R12") (pin "1") (pinfunction "1_1") (pintype "passive"))
      (node (ref "T1") (pin "2") (pinfunction "B_2") (pintype "passive"))
    )
    (net (code "55") (name "Net-(T1-E)") (class "Default")
      (node (ref "R13") (pin "2") (pinfunction "2_2") (pintype "passive"))
      (node (ref "T1") (pin "1") (pinfunction "E_1") (pintype "passive"))
    )
    (net (code "56") (name "Net-(U$5-NON_INV)") (class "Default")
      (node (ref "JP1") (pin "2") (pinfunction "2_2") (pintype "passive"))
      (node (ref "U$5") (pin "INV") (pinfunction "INV_INV") (pintype "bidirectional"))
      (node (ref "U$5") (pin "NONINV") (pinfunction "NON_INV_NONINV") (pintype "bidirectional"))
    )
    (net (code "57") (name "Net-(U2-PB0)") (class "Default")
      (node (ref "J1") (pin "3") (pinfunction "3_3") (pintype "passive"))
      (node (ref "U2") (pin "5") (pinfunction "PB0_5") (pintype "bidirectional"))
    )
    (net (code "58") (name "Net-(U2-PB1)") (class "Default")
      (node (ref "J1") (pin "2") (pinfunction "2_2") (pintype "passive"))
      (node (ref "R46") (pin "2") (pinfunction "2_2") (pintype "passive"))
      (node (ref "U2") (pin "6") (pinfunction "PB1_6") (pintype "bidirectional"))
    )
    (net (code "59") (name "Net-(U2-PB2)") (class "Default")
      (node (ref "J1") (pin "4") (pinfunction "4_4") (pintype "passive"))
      (node (ref "U2") (pin "7") (pinfunction "PB2_7") (pintype "bidirectional"))
    )
    (net (code "60") (name "Net-(U2-PB3)") (class "Default")
      (node (ref "R45") (pin "2") (pinfunction "2_2") (pintype "passive"))
      (node (ref "U2") (pin "2") (pinfunction "PB3_2") (pintype "bidirectional"))
    )
    (net (code "61") (name "Net-(U2-PB4)") (class "Default")
      (node (ref "ONOFF1") (pin "MP") (pinfunction "MP_MP") (pintype "passive"))
      (node (ref "R14") (pin "1") (pinfunction "1_1") (pintype "passive"))
      (node (ref "U2") (pin "3") (pinfunction "PB4_3") (pintype "bidirectional"))
    )
    (net (code "62") (name "Net-(U2-PB5)") (class "Default")
      (node (ref "J1") (pin "6") (pinfunction "6_6") (pintype "passive"))
      (node (ref "U2") (pin "1") (pinfunction "PB5_1") (pintype "bidirectional"))
    )
    (net (code "63") (name "Net-(VOL-S)") (class "Default")
      (node (ref "C24") (pin "+") (pinfunction "+_+") (pintype "passive"))
      (node (ref "VOL") (pin "P$2") (pinfunction "S_P$2") (pintype "passive"))
    )
    (net (code "64") (name "OUT") (class "Default")
      (node (ref "K2") (pin "6") (pinfunction "P_6") (pintype "passive"))
      (node (ref "OK1") (pin "3") (pinfunction "EMIT_3") (pintype "passive"))
      (node (ref "OUT_JACK") (pin "T") (pinfunction "T_T") (pintype "passive"))
    )
    (net (code "65") (name "VB") (class "Default")
      (node (ref "C16") (pin "1") (pinfunction "1_1") (pintype "passive"))
      (node (ref "C20") (pin "+") (pinfunction "+_+") (pintype "passive"))
      (node (ref "C23") (pin "1") (pinfunction "1_1") (pintype "passive"))
      (node (ref "C26") (pin "1") (pinfunction "1_1") (pintype "passive"))
      (node (ref "HP") (pin "P$3") (pinfunction "A_P$3") (pintype "passive"))
      (node (ref "IC1") (pin "10") (pinfunction "+IN_10") (pintype "input"))
      (node (ref "IC1") (pin "12") (pinfunction "+IN_12") (pintype "input"))
      (node (ref "IC1") (pin "5") (pinfunction "+IN_5") (pintype "input"))
      (node (ref "IC2") (pin "8") (pinfunction "OUT_8") (pintype "output"))
      (node (ref "IC2") (pin "9") (pinfunction "-IN_9") (pintype "input"))
      (node (ref "IC4") (pin "3") (pinfunction "+IN_3") (pintype "input"))
      (node (ref "LOW_PASS") (pin "3") (pinfunction "E_3") (pintype "passive"))
      (node (ref "MID_SCOOP") (pin "3") (pinfunction "E_3") (pintype "passive"))
      (node (ref "R11") (pin "1") (pinfunction "1_1") (pintype "passive"))
      (node (ref "R33") (pin "2") (pinfunction "2_2") (pintype "passive"))
      (node (ref "R6") (pin "1") (pinfunction "1_1") (pintype "passive"))
      (node (ref "U$5") (pin "VB") (pinfunction "VB_VB") (pintype "bidirectional"))
      (node (ref "VOL") (pin "P$1") (pinfunction "E_P$1") (pintype "passive"))
    )
    (net (code "66") (name "unconnected-(IC4-ON1-Pad1)") (class "Default")
      (node (ref "IC4") (pin "1") (pinfunction "ON1_1") (pintype "passive"))
    )
    (net (code "67") (name "unconnected-(IC4-ON2-Pad5)") (class "Default")
      (node (ref "IC4") (pin "5") (pinfunction "ON2_5") (pintype "passive"))
    )
    (net (code "68") (name "unconnected-(IC4-OPT-Pad8)") (class "Default")
      (node (ref "IC4") (pin "8") (pinfunction "OPT_8") (pintype "passive"))
    )
    (net (code "69") (name "unconnected-(U$5-CONNECT-PadMAX)") (class "Default")
      (node (ref "U$5") (pin "MAX") (pinfunction "CONNECT_MAX") (pintype "bidirectional"))
    )
    (net (code "70") (name "unconnected-(U$5-CONNECT_MIN-PadMIN)") (class "Default")
      (node (ref "U$5") (pin "MIN") (pinfunction "CONNECT_MIN_MIN") (pintype "bidirectional"))
    )
    (net (code "71") (name "unconnected-(U$5-CONNECT_WIPER-PadWIPER)") (class "Default")
      (node (ref "U$5") (pin "WIPER") (pinfunction "CONNECT_WIPER_WIPER") (pintype "bidirectional"))
    )
  )
)
